# FRONT-UNIT.net
KiCad netlist of a schematic drawn in Altium Designer
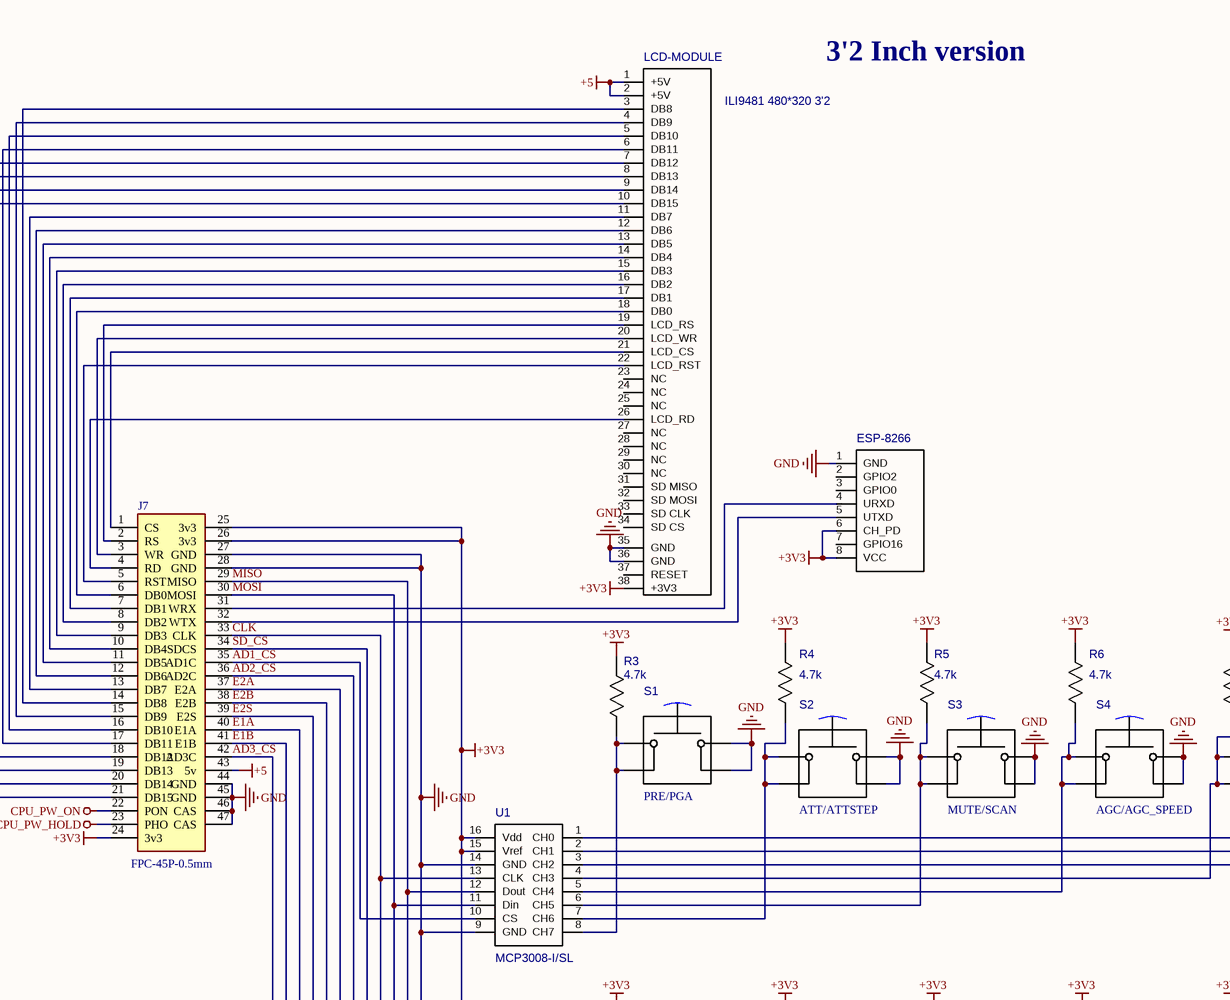
[diagram p0: FRONT-UNIT.SchDoc, top left]
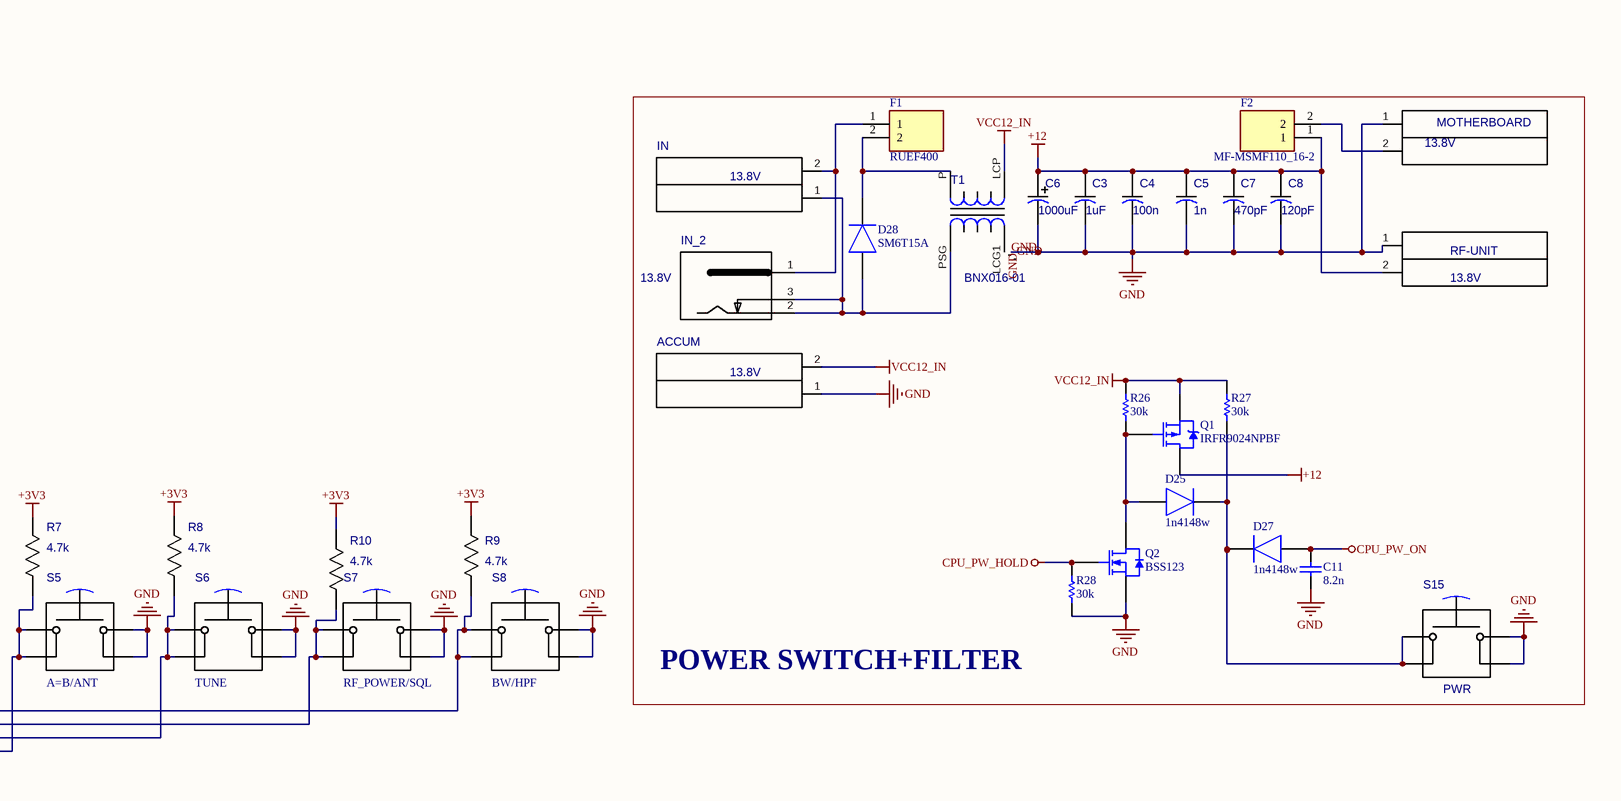
[diagram p1: FRONT-UNIT.SchDoc, top right]
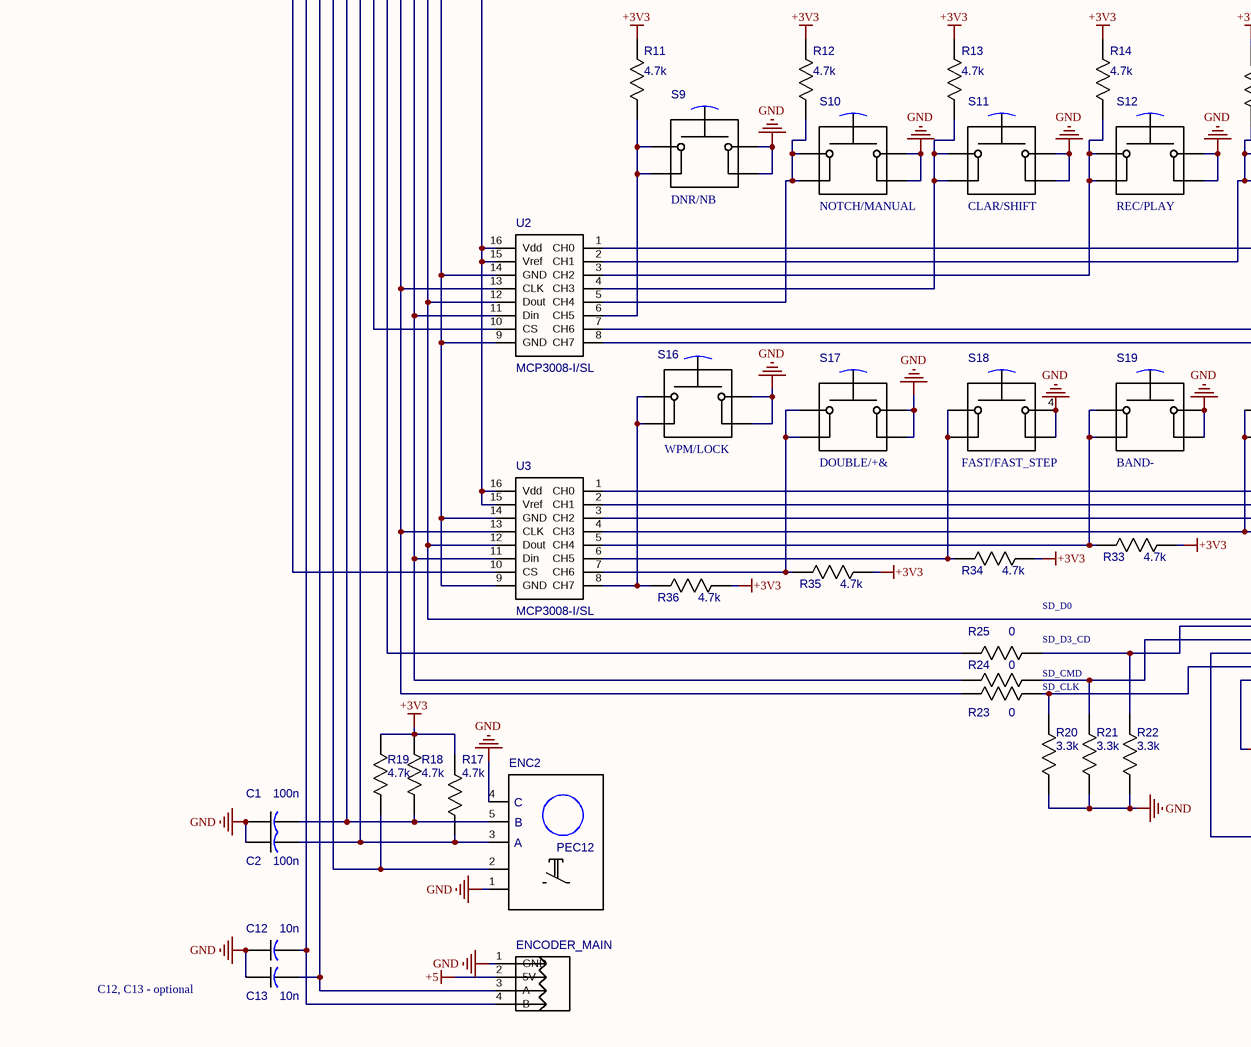
[diagram p2: FRONT-UNIT.SchDoc, bottom left]
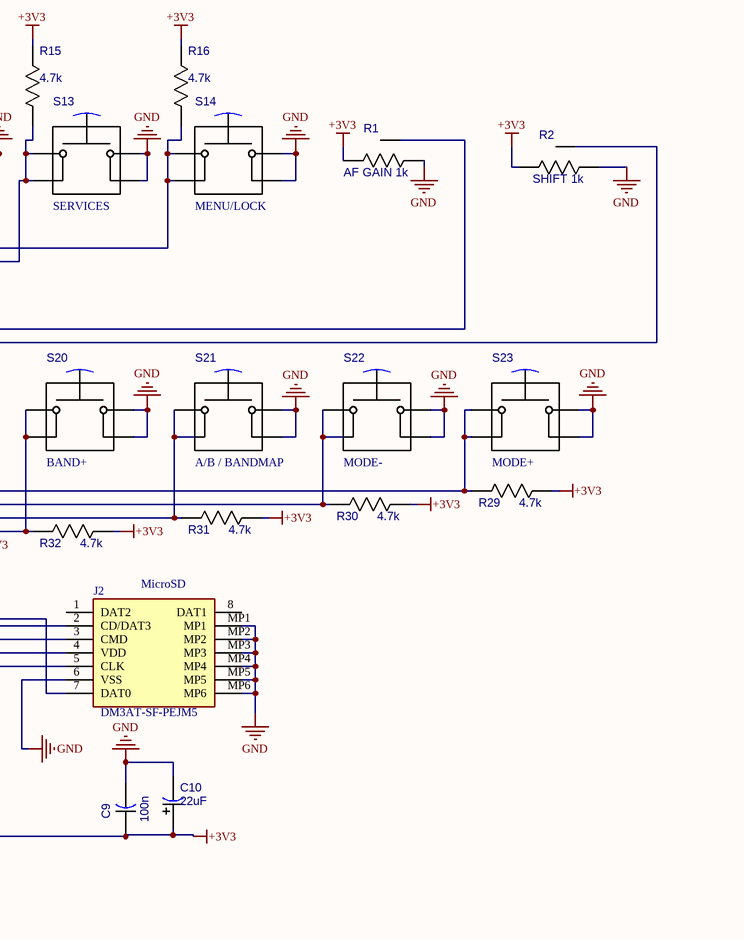
[diagram p3: FRONT-UNIT.SchDoc, bottom right]

(export (version "E")
  (design (tool "Eeschema 10.0.6"))
  (components
    (comp (ref "ACCUM")
      (value "13.8V")
      (footprint "JX2")
      (description "JX2")
      (libsource (lib "*") (part "JX2"))
    )
    (comp (ref "C1")
      (value "100n")
      (footprint "CAP_0805")
      (description "CAP_0805")
      (libsource (lib "*") (part "CAP_0805"))
    )
    (comp (ref "C2")
      (value "100n")
      (footprint "CAP_0805")
      (description "CAP_0805")
      (libsource (lib "*") (part "CAP_0805"))
    )
    (comp (ref "C3")
      (value "1uF")
      (footprint "CAP_1206")
      (description "CAP_1206")
      (libsource (lib "*") (part "CAP_1206"))
    )
    (comp (ref "C4")
      (value "100n")
      (footprint "CAP_1206")
      (description "CAP_1206")
      (libsource (lib "*") (part "CAP_1206"))
    )
    (comp (ref "C5")
      (value "1n")
      (footprint "CAP_1206")
      (description "CAP_1206")
      (libsource (lib "*") (part "CAP_1206"))
    )
    (comp (ref "C6")
      (value "1000uF")
      (footprint "CAP250RP")
      (description "CAP250RP")
      (libsource (lib "*") (part "CAP250RP"))
    )
    (comp (ref "C7")
      (value "470pF")
      (footprint "CAP_1206")
      (description "CAP_1206")
      (libsource (lib "*") (part "CAP_1206"))
    )
    (comp (ref "C8")
      (value "120pF")
      (footprint "CAP_1206")
      (description "CAP_1206")
      (libsource (lib "*") (part "CAP_1206"))
    )
    (comp (ref "C9")
      (value "100n")
      (footprint "CAP_0805")
      (description "CAP_0805")
      (libsource (lib "*") (part "CAP_0805"))
    )
    (comp (ref "C10")
      (value "22uF")
      (footprint "EEEFC_sizeB")
      (description "EEEFC_sizeB")
      (libsource (lib "*") (part "EEEFC_sizeB"))
    )
    (comp (ref "C11")
      (value "8.2n")
      (footprint "CAPC2013X94X50LL20T25")
      (description "CAP_1206")
      (fields
        (field (name "MANUFACTURER") "AVX Interconnect / Elco")
        (field (name "PART NUMBER") "08055C822KAT2A")
      )
      (libsource (lib "Altium Content Vault") (part "CAP"))
    )
    (comp (ref "C12")
      (value "10n")
      (footprint "CAP_0805")
      (description "CAP_0805")
      (libsource (lib "*") (part "CAP_0805"))
    )
    (comp (ref "C13")
      (value "10n")
      (footprint "CAP_0805")
      (description "CAP_0805")
      (libsource (lib "*") (part "CAP_0805"))
    )
    (comp (ref "D25")
      (value "1n4148w")
      (footprint "SamacSys:SOD3716X135N")
      (description "Diode")
      (libsource (lib "*") (part "1n4148w"))
    )
    (comp (ref "D27")
      (value "1n4148w")
      (footprint "SamacSys:SOD3716X135N")
      (description "Diode")
      (libsource (lib "*") (part "1n4148w"))
    )
    (comp (ref "D28")
      (value "SM6T15A")
      (footprint "SamacSys:SMBJ36CATR")
      (description "Diode")
      (fields (field (name "MOUSER PART NUMBER") "511-SM6T15A") (field (name "RS PART NUMBER") "4864915P"))
      (libsource (lib "*") (part "SM6T15A"))
    )
    (comp (ref "ENC2") (value "PEC12") (footprint "PEC12") (libsource (lib "*") (part "PEC12")))
    (comp (ref "ENCODER_MAIN")
      (value "OPTICAL ENCODER")
      (footprint "644456-4")
      (libsource (lib "*") (part "644456-4"))
    )
    (comp (ref "ESP-8266")
      (value "ESP-01 ESP8266")
      (footprint "ESP-01 ESP8266")
      (libsource (lib "*") (part "ESP-01 ESP8266"))
    )
    (comp (ref "F1")
      (value "RUEF400")
      (footprint "SamacSys:RUEF400")
      (description "Fuse")
      (fields (field (name "MOUSER PART NUMBER") "650-RUEF400") (field (name "RS PART NUMBER") "5176837P"))
      (libsource (lib "*") (part "RUEF400"))
    )
    (comp (ref "F2")
      (value "MF-MSMF110_16-2")
      (footprint "SamacSys:FUSC4632X85N")
      (description "Fuse")
      (fields
        (field (name "MANUFACTURER_PART_NUMBER") "MF-MSMF110/16-2")
        (field (name "MOUSER PART NUMBER") "652-MF-MSMF110/16-2")
      )
      (libsource (lib "*") (part "MF-MSMF110_16-2"))
    )
    (comp (ref "IN") (value "13.8V") (footprint "JX2") (description "JX2") (libsource (lib "*") (part "JX2")))
    (comp (ref "IN_2")
      (value "13.8V")
      (footprint "PJ-050B")
      (description "PJ-050B")
      (libsource (lib "*") (part "PJ-050B"))
    )
    (comp (ref "J2")
      (value "DM3AT-SF-PEJM5")
      (footprint "SamacSys:DM3ATSFPEJM5")
      (description "Connector")
      (libsource (lib "*") (part "DM3AT-SF-PEJM5"))
    )
    (comp (ref "J7")
      (value "FPC-45P-0.5mm")
      (footprint "FRONT-UNIT:FH12S45S05SH60")
      (description "Connector")
      (fields
        (field (name "MANUFACTURER_PART_NUMBER") "FH12S-45S-0.5SH(55)")
        (field (name "MOUSER PART NUMBER") "798-FH12S-45S-05SH55")
      )
      (libsource (lib "*") (part "FH12S-45S-0.5SH_55_"))
    )
    (comp (ref "LCD-MODULE")
      (value "ILI9481 480*320 3'2")
      (footprint "LCD-MODULE-3.2-480-320")
      (description "LCD-MODULE_3'2_480х320")
      (libsource (lib "FRONT-UNIT") (part "LCD-MODULE_3'2_480х320"))
    )
    (comp (ref "MOTHERBOARD")
      (value "13.8V")
      (footprint "JX2")
      (description "JX2")
      (libsource (lib "*") (part "JX2"))
    )
    (comp (ref "Q1")
      (value "IRFR9024NPBF")
      (footprint "ONSC-DPAK-3-369C-01_V")
      (description "IRFR9024NPBF, Транзистор, Р-канал 55В 11А")
      (fields (field (name "MANUFACTURER") "On Semiconductor") (field (name "PARTNUMBER") "NTD2955G"))
      (libsource (lib "Altium Content Vault") (part "ONSC-PMOS-G1S3D4-3_B"))
    )
    (comp (ref "Q2")
      (value "BSS123")
      (footprint "FAIR-SOT23-3_V")
      (fields (field (name "MANUFACTURER") "Fairchild"))
      (libsource (lib "Altium Content Vault") (part "NEMOS-GSD-3"))
    )
    (comp (ref "R1")
      (value "AF GAIN 1k")
      (footprint "PTV09")
      (description "Adjustable Resistor PTV09")
      (fields (field (name "Comment") "ptv09a-4225f-b102"))
      (libsource (lib "*") (part "PTV09"))
    )
    (comp (ref "R2")
      (value "SHIFT 1k")
      (footprint "PTV09")
      (description "Adjustable Resistor PTV09")
      (fields (field (name "Comment") "ptv09a-4225f-b102"))
      (libsource (lib "*") (part "PTV09"))
    )
    (comp (ref "R3")
      (value "4.7k")
      (footprint "RES_0805")
      (description "RES_0805")
      (libsource (lib "*") (part "RES_0805"))
    )
    (comp (ref "R4")
      (value "4.7k")
      (footprint "RES_0805")
      (description "RES_0805")
      (libsource (lib "*") (part "RES_0805"))
    )
    (comp (ref "R5")
      (value "4.7k")
      (footprint "RES_0805")
      (description "RES_0805")
      (libsource (lib "*") (part "RES_0805"))
    )
    (comp (ref "R6")
      (value "4.7k")
      (footprint "RES_0805")
      (description "RES_0805")
      (libsource (lib "*") (part "RES_0805"))
    )
    (comp (ref "R7")
      (value "4.7k")
      (footprint "RES_0805")
      (description "RES_0805")
      (libsource (lib "*") (part "RES_0805"))
    )
    (comp (ref "R8")
      (value "4.7k")
      (footprint "RES_0805")
      (description "RES_0805")
      (libsource (lib "*") (part "RES_0805"))
    )
    (comp (ref "R9")
      (value "4.7k")
      (footprint "RES_0805")
      (description "RES_0805")
      (libsource (lib "*") (part "RES_0805"))
    )
    (comp (ref "R10")
      (value "4.7k")
      (footprint "RES_0805")
      (description "RES_0805")
      (libsource (lib "*") (part "RES_0805"))
    )
    (comp (ref "R11")
      (value "4.7k")
      (footprint "RES_0805")
      (description "RES_0805")
      (libsource (lib "*") (part "RES_0805"))
    )
    (comp (ref "R12")
      (value "4.7k")
      (footprint "RES_0805")
      (description "RES_0805")
      (libsource (lib "*") (part "RES_0805"))
    )
    (comp (ref "R13")
      (value "4.7k")
      (footprint "RES_0805")
      (description "RES_0805")
      (libsource (lib "*") (part "RES_0805"))
    )
    (comp (ref "R14")
      (value "4.7k")
      (footprint "RES_0805")
      (description "RES_0805")
      (libsource (lib "*") (part "RES_0805"))
    )
    (comp (ref "R15")
      (value "4.7k")
      (footprint "RES_0805")
      (description "RES_0805")
      (libsource (lib "*") (part "RES_0805"))
    )
    (comp (ref "R16")
      (value "4.7k")
      (footprint "RES_0805")
      (description "RES_0805")
      (libsource (lib "*") (part "RES_0805"))
    )
    (comp (ref "R17")
      (value "4.7k")
      (footprint "RES_0805")
      (description "RES_0805")
      (libsource (lib "*") (part "RES_0805"))
    )
    (comp (ref "R18")
      (value "4.7k")
      (footprint "RES_0805")
      (description "RES_0805")
      (libsource (lib "*") (part "RES_0805"))
    )
    (comp (ref "R19")
      (value "4.7k")
      (footprint "RES_0805")
      (description "RES_0805")
      (libsource (lib "*") (part "RES_0805"))
    )
    (comp (ref "R20")
      (value "3.3k")
      (footprint "RES_0805")
      (description "RES_0805")
      (libsource (lib "*") (part "RES_0805"))
    )
    (comp (ref "R21")
      (value "3.3k")
      (footprint "RES_0805")
      (description "RES_0805")
      (libsource (lib "*") (part "RES_0805"))
    )
    (comp (ref "R22")
      (value "3.3k")
      (footprint "RES_0805")
      (description "RES_0805")
      (libsource (lib "*") (part "RES_0805"))
    )
    (comp (ref "R23")
      (value "0")
      (footprint "RES_0805")
      (description "RES_0805")
      (libsource (lib "*") (part "RES_0805"))
    )
    (comp (ref "R24")
      (value "0")
      (footprint "RES_0805")
      (description "RES_0805")
      (libsource (lib "*") (part "RES_0805"))
    )
    (comp (ref "R25")
      (value "0")
      (footprint "RES_0805")
      (description "RES_0805")
      (libsource (lib "*") (part "RES_0805"))
    )
    (comp (ref "R26")
      (value "30k")
      (footprint "RESC2013X60X40NL20T25")
      (description "RES_0805")
      (fields (field (name "MANUFACTURER") "Panasonic") (field (name "PART NUMBER") "ERA-6AEB303V"))
      (libsource (lib "Altium Content Vault") (part "RES"))
    )
    (comp (ref "R27")
      (value "30k")
      (footprint "RESC2013X60X40NL20T25")
      (description "RES_0805")
      (fields (field (name "MANUFACTURER") "Panasonic") (field (name "PART NUMBER") "ERA-6AEB303V"))
      (libsource (lib "Altium Content Vault") (part "RES"))
    )
    (comp (ref "R28")
      (value "30k")
      (footprint "RESC2013X60X40NL20T25")
      (description "RES_0805")
      (fields (field (name "MANUFACTURER") "Panasonic") (field (name "PART NUMBER") "ERA-6AEB303V"))
      (libsource (lib "Altium Content Vault") (part "RES"))
    )
    (comp (ref "R29")
      (value "4.7k")
      (footprint "RES_0805")
      (description "RES_0805")
      (libsource (lib "*") (part "RES_0805"))
    )
    (comp (ref "R30")
      (value "4.7k")
      (footprint "RES_0805")
      (description "RES_0805")
      (libsource (lib "*") (part "RES_0805"))
    )
    (comp (ref "R31")
      (value "4.7k")
      (footprint "RES_0805")
      (description "RES_0805")
      (libsource (lib "*") (part "RES_0805"))
    )
    (comp (ref "R32")
      (value "4.7k")
      (footprint "RES_0805")
      (description "RES_0805")
      (libsource (lib "*") (part "RES_0805"))
    )
    (comp (ref "R33")
      (value "4.7k")
      (footprint "RES_0805")
      (description "RES_0805")
      (libsource (lib "*") (part "RES_0805"))
    )
    (comp (ref "R34")
      (value "4.7k")
      (footprint "RES_0805")
      (description "RES_0805")
      (libsource (lib "*") (part "RES_0805"))
    )
    (comp (ref "R35")
      (value "4.7k")
      (footprint "RES_0805")
      (description "RES_0805")
      (libsource (lib "*") (part "RES_0805"))
    )
    (comp (ref "R36")
      (value "4.7k")
      (footprint "RES_0805")
      (description "RES_0805")
      (libsource (lib "*") (part "RES_0805"))
    )
    (comp (ref "RF-UNIT")
      (value "13.8V")
      (footprint "JX2")
      (description "JX2")
      (libsource (lib "*") (part "JX2"))
    )
    (comp (ref "S1")
      (value "PTS645SK50LFS")
      (footprint "PTS645SK50LFS")
      (fields (field (name "LCSC PART #") "test"))
      (libsource (lib "*") (part "PTS645SK50LFS"))
    )
    (comp (ref "S2")
      (value "PTS645SK50LFS")
      (footprint "PTS645SK50LFS")
      (libsource (lib "*") (part "PTS645SK50LFS"))
    )
    (comp (ref "S3")
      (value "PTS645SK50LFS")
      (footprint "PTS645SK50LFS")
      (libsource (lib "*") (part "PTS645SK50LFS"))
    )
    (comp (ref "S4")
      (value "PTS645SK50LFS")
      (footprint "PTS645SK50LFS")
      (libsource (lib "*") (part "PTS645SK50LFS"))
    )
    (comp (ref "S5")
      (value "PTS645SK50LFS")
      (footprint "PTS645SK50LFS")
      (libsource (lib "*") (part "PTS645SK50LFS"))
    )
    (comp (ref "S6")
      (value "PTS645SK50LFS")
      (footprint "PTS645SK50LFS")
      (libsource (lib "*") (part "PTS645SK50LFS"))
    )
    (comp (ref "S7")
      (value "PTS645SK50LFS")
      (footprint "PTS645SK50LFS")
      (libsource (lib "*") (part "PTS645SK50LFS"))
    )
    (comp (ref "S8")
      (value "PTS645SK50LFS")
      (footprint "PTS645SK50LFS")
      (libsource (lib "*") (part "PTS645SK50LFS"))
    )
    (comp (ref "S9")
      (value "PTS645SK50LFS")
      (footprint "PTS645SK50LFS")
      (libsource (lib "*") (part "PTS645SK50LFS"))
    )
    (comp (ref "S10")
      (value "PTS645SK50LFS")
      (footprint "PTS645SK50LFS")
      (libsource (lib "*") (part "PTS645SK50LFS"))
    )
    (comp (ref "S11")
      (value "PTS645SK50LFS")
      (footprint "PTS645SK50LFS")
      (libsource (lib "*") (part "PTS645SK50LFS"))
    )
    (comp (ref "S12")
      (value "PTS645SK50LFS")
      (footprint "PTS645SK50LFS")
      (libsource (lib "*") (part "PTS645SK50LFS"))
    )
    (comp (ref "S13")
      (value "PTS645SK50LFS")
      (footprint "PTS645SK50LFS")
      (libsource (lib "*") (part "PTS645SK50LFS"))
    )
    (comp (ref "S14")
      (value "PTS645SK50LFS")
      (footprint "PTS645SK50LFS")
      (libsource (lib "*") (part "PTS645SK50LFS"))
    )
    (comp (ref "S15")
      (value "PWR")
      (footprint "PTS645SK50LFS")
      (description "PTS645SK50LFS")
      (libsource (lib "*") (part "PTS645SK50LFS"))
    )
    (comp (ref "S16")
      (value "PTS645SK50LFS")
      (footprint "PTS645SK50LFS")
      (libsource (lib "*") (part "PTS645SK50LFS"))
    )
    (comp (ref "S17")
      (value "PTS645SK50LFS")
      (footprint "PTS645SK50LFS")
      (libsource (lib "*") (part "PTS645SK50LFS"))
    )
    (comp (ref "S18")
      (value "PTS645SK50LFS")
      (footprint "PTS645SK50LFS")
      (libsource (lib "") (part "PTS645SK50LFS_1"))
    )
    (comp (ref "S19")
      (value "PTS645SK50LFS")
      (footprint "PTS645SK50LFS")
      (libsource (lib "*") (part "PTS645SK50LFS"))
    )
    (comp (ref "S20")
      (value "PTS645SK50LFS")
      (footprint "PTS645SK50LFS")
      (libsource (lib "*") (part "PTS645SK50LFS"))
    )
    (comp (ref "S21")
      (value "PTS645SK50LFS")
      (footprint "PTS645SK50LFS")
      (libsource (lib "*") (part "PTS645SK50LFS"))
    )
    (comp (ref "S22")
      (value "PTS645SK50LFS")
      (footprint "PTS645SK50LFS")
      (libsource (lib "*") (part "PTS645SK50LFS"))
    )
    (comp (ref "S23")
      (value "PTS645SK50LFS")
      (footprint "PTS645SK50LFS")
      (libsource (lib "*") (part "PTS645SK50LFS"))
    )
    (comp (ref "T1")
      (value "BNX016-01")
      (footprint "TRANSF_ICORE")
      (libsource (lib "*") (part "TRANSF_ICORE"))
    )
    (comp (ref "U1")
      (value "MCP3008-I/SL")
      (footprint "MCP3008-I/SL")
      (libsource (lib "*") (part "MCP3008-I/SL"))
    )
    (comp (ref "U2")
      (value "MCP3008-I/SL")
      (footprint "MCP3008-I/SL")
      (libsource (lib "*") (part "MCP3008-I/SL"))
    )
    (comp (ref "U3")
      (value "MCP3008-I/SL")
      (footprint "MCP3008-I/SL")
      (libsource (lib "*") (part "MCP3008-I/SL"))
    )
  )
  (nets
    (net (code "1") (name "+3V3") (class "Default")
      (node (ref "C10") (pin "1") (pinfunction "PLUS_1") (pintype "passive"))
      (node (ref "C9") (pin "1") (pinfunction "1_1") (pintype "passive"))
      (node (ref "ESP-8266") (pin "6") (pinfunction "CH_PD_6") (pintype "passive"))
      (node (ref "ESP-8266") (pin "8") (pinfunction "VCC_8") (pintype "passive"))
      (node (ref "J2") (pin "4") (pinfunction "VDD_4") (pintype "passive"))
      (node (ref "J7") (pin "24") (pinfunction "3v3_24") (pintype "passive"))
      (node (ref "J7") (pin "25") (pinfunction "3v3_25") (pintype "passive"))
      (node (ref "J7") (pin "26") (pinfunction "3v3_26") (pintype "passive"))
      (node (ref "LCD-MODULE") (pin "38") (pinfunction "+3V3_38") (pintype "passive"))
      (node (ref "R1") (pin "1") (pinfunction "CW_1") (pintype "passive"))
      (node (ref "R10") (pin "2") (pinfunction "2_2") (pintype "passive"))
      (node (ref "R11") (pin "2") (pinfunction "2_2") (pintype "passive"))
      (node (ref "R12") (pin "2") (pinfunction "2_2") (pintype "passive"))
      (node (ref "R13") (pin "2") (pinfunction "2_2") (pintype "passive"))
      (node (ref "R14") (pin "2") (pinfunction "2_2") (pintype "passive"))
      (node (ref "R15") (pin "2") (pinfunction "2_2") (pintype "passive"))
      (node (ref "R16") (pin "2") (pinfunction "2_2") (pintype "passive"))
      (node (ref "R17") (pin "2") (pinfunction "2_2") (pintype "passive"))
      (node (ref "R18") (pin "2") (pinfunction "2_2") (pintype "passive"))
      (node (ref "R19") (pin "2") (pinfunction "2_2") (pintype "passive"))
      (node (ref "R2") (pin "1") (pinfunction "CW_1") (pintype "passive"))
      (node (ref "R29") (pin "2") (pinfunction "2_2") (pintype "passive"))
      (node (ref "R3") (pin "2") (pinfunction "2_2") (pintype "passive"))
      (node (ref "R30") (pin "2") (pinfunction "2_2") (pintype "passive"))
      (node (ref "R31") (pin "2") (pinfunction "2_2") (pintype "passive"))
      (node (ref "R32") (pin "2") (pinfunction "2_2") (pintype "passive"))
      (node (ref "R33") (pin "2") (pinfunction "2_2") (pintype "passive"))
      (node (ref "R34") (pin "2") (pinfunction "2_2") (pintype "passive"))
      (node (ref "R35") (pin "2") (pinfunction "2_2") (pintype "passive"))
      (node (ref "R36") (pin "2") (pinfunction "2_2") (pintype "passive"))
      (node (ref "R4") (pin "2") (pinfunction "2_2") (pintype "passive"))
      (node (ref "R5") (pin "2") (pinfunction "2_2") (pintype "passive"))
      (node (ref "R6") (pin "2") (pinfunction "2_2") (pintype "passive"))
      (node (ref "R7") (pin "2") (pinfunction "2_2") (pintype "passive"))
      (node (ref "R8") (pin "2") (pinfunction "2_2") (pintype "passive"))
      (node (ref "R9") (pin "2") (pinfunction "2_2") (pintype "passive"))
      (node (ref "U1") (pin "15") (pinfunction "Vref_15") (pintype "passive"))
      (node (ref "U1") (pin "16") (pinfunction "Vdd_16") (pintype "passive"))
      (node (ref "U2") (pin "15") (pinfunction "Vref_15") (pintype "passive"))
      (node (ref "U2") (pin "16") (pinfunction "Vdd_16") (pintype "passive"))
      (node (ref "U3") (pin "15") (pinfunction "Vref_15") (pintype "passive"))
      (node (ref "U3") (pin "16") (pinfunction "Vdd_16") (pintype "passive"))
    )
    (net (code "2") (name "+5") (class "Default")
      (node (ref "ENCODER_MAIN") (pin "2") (pinfunction "5V_2") (pintype "passive"))
      (node (ref "J7") (pin "43") (pinfunction "5v_43") (pintype "passive"))
      (node (ref "LCD-MODULE") (pin "1") (pinfunction "+5V_1") (pintype "passive"))
      (node (ref "LCD-MODULE") (pin "2") (pinfunction "+5V_2") (pintype "passive"))
    )
    (net (code "3") (name "+12") (class "Default")
      (node (ref "C3") (pin "1") (pinfunction "1_1") (pintype "passive"))
      (node (ref "C4") (pin "1") (pinfunction "1_1") (pintype "passive"))
      (node (ref "C5") (pin "1") (pinfunction "1_1") (pintype "passive"))
      (node (ref "C6") (pin "1") (pinfunction "PLUS_1") (pintype "passive"))
      (node (ref "C7") (pin "1") (pinfunction "1_1") (pintype "passive"))
      (node (ref "C8") (pin "1") (pinfunction "1_1") (pintype "passive"))
      (node (ref "F2") (pin "1") (pinfunction "1_1") (pintype "passive"))
      (node (ref "Q1") (pin "4") (pinfunction "D_4") (pintype "passive"))
      (node (ref "RF-UNIT") (pin "2") (pinfunction "1_2") (pintype "passive"))
    )
    (net (code "4") (name "/AD1_CS") (class "Default")
      (node (ref "J7") (pin "35") (pinfunction "AD1C_35") (pintype "passive"))
      (node (ref "U1") (pin "10") (pinfunction "CS_10") (pintype "passive"))
    )
    (net (code "5") (name "/AD2_CS") (class "Default")
      (node (ref "J7") (pin "36") (pinfunction "AD2C_36") (pintype "passive"))
      (node (ref "U2") (pin "10") (pinfunction "CS_10") (pintype "passive"))
    )
    (net (code "6") (name "/AD3_CS") (class "Default")
      (node (ref "J7") (pin "42") (pinfunction "AD3C_42") (pintype "passive"))
      (node (ref "U3") (pin "10") (pinfunction "CS_10") (pintype "passive"))
    )
    (net (code "7") (name "/CLK") (class "Default")
      (node (ref "J7") (pin "33") (pinfunction "CLK_33") (pintype "passive"))
      (node (ref "R23") (pin "2") (pinfunction "2_2") (pintype "passive"))
      (node (ref "U1") (pin "13") (pinfunction "CLK_13") (pintype "passive"))
      (node (ref "U2") (pin "13") (pinfunction "CLK_13") (pintype "passive"))
      (node (ref "U3") (pin "13") (pinfunction "CLK_13") (pintype "passive"))
    )
    (net (code "8") (name "/E1A") (class "Default")
      (node (ref "C13") (pin "2") (pinfunction "2_2") (pintype "passive"))
      (node (ref "ENCODER_MAIN") (pin "3") (pinfunction "A_3") (pintype "passive"))
      (node (ref "J7") (pin "40") (pinfunction "E1A_40") (pintype "passive"))
    )
    (net (code "9") (name "/E1B") (class "Default")
      (node (ref "C12") (pin "2") (pinfunction "2_2") (pintype "passive"))
      (node (ref "ENCODER_MAIN") (pin "4") (pinfunction "B_4") (pintype "passive"))
      (node (ref "J7") (pin "41") (pinfunction "E1B_41") (pintype "passive"))
    )
    (net (code "10") (name "/E2A") (class "Default")
      (node (ref "C2") (pin "2") (pinfunction "2_2") (pintype "passive"))
      (node (ref "ENC2") (pin "3") (pinfunction "A_3") (pintype "passive"))
      (node (ref "J7") (pin "37") (pinfunction "E2A_37") (pintype "passive"))
      (node (ref "R17") (pin "1") (pinfunction "1_1") (pintype "passive"))
    )
    (net (code "11") (name "/E2B") (class "Default")
      (node (ref "C1") (pin "2") (pinfunction "2_2") (pintype "passive"))
      (node (ref "ENC2") (pin "5") (pinfunction "B_5") (pintype "passive"))
      (node (ref "J7") (pin "38") (pinfunction "E2B_38") (pintype "passive"))
      (node (ref "R18") (pin "1") (pinfunction "1_1") (pintype "passive"))
    )
    (net (code "12") (name "/E2S") (class "Default")
      (node (ref "ENC2") (pin "2") (pinfunction "2_2") (pintype "passive"))
      (node (ref "J7") (pin "39") (pinfunction "E2S_39") (pintype "passive"))
      (node (ref "R19") (pin "1") (pinfunction "1_1") (pintype "passive"))
    )
    (net (code "13") (name "/MISO") (class "Default")
      (node (ref "J2") (pin "7") (pinfunction "DAT0_7") (pintype "passive"))
      (node (ref "J7") (pin "29") (pinfunction "MISO_29") (pintype "passive"))
      (node (ref "U1") (pin "12") (pinfunction "Dout_12") (pintype "passive"))
      (node (ref "U2") (pin "12") (pinfunction "Dout_12") (pintype "passive"))
      (node (ref "U3") (pin "12") (pinfunction "Dout_12") (pintype "passive"))
    )
    (net (code "14") (name "/MOSI") (class "Default")
      (node (ref "J7") (pin "30") (pinfunction "MOSI_30") (pintype "passive"))
      (node (ref "R24") (pin "2") (pinfunction "2_2") (pintype "passive"))
      (node (ref "U1") (pin "11") (pinfunction "Din_11") (pintype "passive"))
      (node (ref "U2") (pin "11") (pinfunction "Din_11") (pintype "passive"))
      (node (ref "U3") (pin "11") (pinfunction "Din_11") (pintype "passive"))
    )
    (net (code "15") (name "/SD_CS") (class "Default")
      (node (ref "J7") (pin "34") (pinfunction "SDCS_34") (pintype "passive"))
      (node (ref "R25") (pin "2") (pinfunction "2_2") (pintype "passive"))
    )
    (net (code "16") (name "CPU_PW_HOLD") (class "Default")
      (node (ref "J7") (pin "23") (pinfunction "PHO_23") (pintype "passive"))
      (node (ref "Q2") (pin "1") (pinfunction "G_1") (pintype "passive"))
      (node (ref "R28") (pin "2") (pinfunction "2_2") (pintype "passive"))
    )
    (net (code "17") (name "CPU_PW_ON") (class "Default")
      (node (ref "C11") (pin "2") (pinfunction "2_2") (pintype "passive"))
      (node (ref "D27") (pin "2") (pinfunction "A_2") (pintype "passive"))
      (node (ref "J7") (pin "22") (pinfunction "PON_22") (pintype "passive"))
    )
    (net (code "18") (name "GND") (class "Default")
      (node (ref "ACCUM") (pin "1") (pinfunction "2_1") (pintype "passive"))
      (node (ref "C1") (pin "1") (pinfunction "1_1") (pintype "passive"))
      (node (ref "C10") (pin "2") (pinfunction "MINUS_2") (pintype "passive"))
      (node (ref "C11") (pin "1") (pinfunction "1_1") (pintype "passive"))
      (node (ref "C12") (pin "1") (pinfunction "1_1") (pintype "passive"))
      (node (ref "C13") (pin "1") (pinfunction "1_1") (pintype "passive"))
      (node (ref "C2") (pin "1") (pinfunction "1_1") (pintype "passive"))
      (node (ref "C3") (pin "2") (pinfunction "2_2") (pintype "passive"))
      (node (ref "C4") (pin "2") (pinfunction "2_2") (pintype "passive"))
      (node (ref "C5") (pin "2") (pinfunction "2_2") (pintype "passive"))
      (node (ref "C6") (pin "2") (pinfunction "MINUS_2") (pintype "passive"))
      (node (ref "C7") (pin "2") (pinfunction "2_2") (pintype "passive"))
      (node (ref "C8") (pin "2") (pinfunction "2_2") (pintype "passive"))
      (node (ref "C9") (pin "2") (pinfunction "2_2") (pintype "passive"))
      (node (ref "ENC2") (pin "1") (pinfunction "1_1") (pintype "passive"))
      (node (ref "ENC2") (pin "4") (pinfunction "C_4") (pintype "passive"))
      (node (ref "ENCODER_MAIN") (pin "1") (pinfunction "GND_1") (pintype "passive"))
      (node (ref "ESP-8266") (pin "1") (pinfunction "GND_1") (pintype "passive"))
      (node (ref "J2") (pin "6") (pinfunction "VSS_6") (pintype "passive"))
      (node (ref "J2") (pin "MP1") (pinfunction "MP1_MP1") (pintype "passive"))
      (node (ref "J2") (pin "MP2") (pinfunction "MP2_MP2") (pintype "passive"))
      (node (ref "J2") (pin "MP3") (pinfunction "MP3_MP3") (pintype "passive"))
      (node (ref "J2") (pin "MP4") (pinfunction "MP4_MP4") (pintype "passive"))
      (node (ref "J2") (pin "MP5") (pinfunction "MP5_MP5") (pintype "passive"))
      (node (ref "J2") (pin "MP6") (pinfunction "MP6_MP6") (pintype "passive"))
      (node (ref "J7") (pin "27") (pinfunction "GND_27") (pintype "passive"))
      (node (ref "J7") (pin "28") (pinfunction "GND_28") (pintype "passive"))
      (node (ref "J7") (pin "44") (pinfunction "GND_44") (pintype "passive"))
      (node (ref "J7") (pin "45") (pinfunction "GND_45") (pintype "passive"))
      (node (ref "J7") (pin "46") (pinfunction "CAS_46") (pintype "passive"))
      (node (ref "J7") (pin "47") (pinfunction "CAS_47") (pintype "passive"))
      (node (ref "LCD-MODULE") (pin "35") (pinfunction "GND_35") (pintype "passive"))
      (node (ref "LCD-MODULE") (pin "36") (pinfunction "GND_36") (pintype "passive"))
      (node (ref "MOTHERBOARD") (pin "1") (pinfunction "2_1") (pintype "passive"))
      (node (ref "Q2") (pin "2") (pinfunction "S_2") (pintype "passive"))
      (node (ref "R1") (pin "3") (pinfunction "CCW_3") (pintype "passive"))
      (node (ref "R2") (pin "3") (pinfunction "CCW_3") (pintype "passive"))
      (node (ref "R20") (pin "1") (pinfunction "1_1") (pintype "passive"))
      (node (ref "R21") (pin "1") (pinfunction "1_1") (pintype "passive"))
      (node (ref "R22") (pin "1") (pinfunction "1_1") (pintype "passive"))
      (node (ref "R28") (pin "1") (pinfunction "1_1") (pintype "passive"))
      (node (ref "RF-UNIT") (pin "1") (pinfunction "2_1") (pintype "passive"))
      (node (ref "S1") (pin "3") (pinfunction "B_3") (pintype "passive"))
      (node (ref "S1") (pin "4") (pinfunction "B_4") (pintype "passive"))
      (node (ref "S10") (pin "3") (pinfunction "B_3") (pintype "passive"))
      (node (ref "S10") (pin "4") (pinfunction "B_4") (pintype "passive"))
      (node (ref "S11") (pin "3") (pinfunction "B_3") (pintype "passive"))
      (node (ref "S11") (pin "4") (pinfunction "B_4") (pintype "passive"))
      (node (ref "S12") (pin "3") (pinfunction "B_3") (pintype "passive"))
      (node (ref "S12") (pin "4") (pinfunction "B_4") (pintype "passive"))
      (node (ref "S13") (pin "3") (pinfunction "B_3") (pintype "passive"))
      (node (ref "S13") (pin "4") (pinfunction "B_4") (pintype "passive"))
      (node (ref "S14") (pin "3") (pinfunction "B_3") (pintype "passive"))
      (node (ref "S14") (pin "4") (pinfunction "B_4") (pintype "passive"))
      (node (ref "S15") (pin "3") (pinfunction "B_3") (pintype "passive"))
      (node (ref "S15") (pin "4") (pinfunction "B_4") (pintype "passive"))
      (node (ref "S16") (pin "3") (pinfunction "B_3") (pintype "passive"))
      (node (ref "S16") (pin "4") (pinfunction "B_4") (pintype "passive"))
      (node (ref "S17") (pin "3") (pinfunction "B_3") (pintype "passive"))
      (node (ref "S17") (pin "4") (pinfunction "B_4") (pintype "passive"))
      (node (ref "S18") (pin "3") (pinfunction "B_3") (pintype "passive"))
      (node (ref "S18") (pin "4") (pinfunction "B_4") (pintype "passive"))
      (node (ref "S19") (pin "3") (pinfunction "B_3") (pintype "passive"))
      (node (ref "S19") (pin "4") (pinfunction "B_4") (pintype "passive"))
      (node (ref "S2") (pin "3") (pinfunction "B_3") (pintype "passive"))
      (node (ref "S2") (pin "4") (pinfunction "B_4") (pintype "passive"))
      (node (ref "S20") (pin "3") (pinfunction "B_3") (pintype "passive"))
      (node (ref "S20") (pin "4") (pinfunction "B_4") (pintype "passive"))
      (node (ref "S21") (pin "3") (pinfunction "B_3") (pintype "passive"))
      (node (ref "S21") (pin "4") (pinfunction "B_4") (pintype "passive"))
      (node (ref "S22") (pin "3") (pinfunction "B_3") (pintype "passive"))
      (node (ref "S22") (pin "4") (pinfunction "B_4") (pintype "passive"))
      (node (ref "S23") (pin "3") (pinfunction "B_3") (pintype "passive"))
      (node (ref "S23") (pin "4") (pinfunction "B_4") (pintype "passive"))
      (node (ref "S3") (pin "3") (pinfunction "B_3") (pintype "passive"))
      (node (ref "S3") (pin "4") (pinfunction "B_4") (pintype "passive"))
      (node (ref "S4") (pin "3") (pinfunction "B_3") (pintype "passive"))
      (node (ref "S4") (pin "4") (pinfunction "B_4") (pintype "passive"))
      (node (ref "S5") (pin "3") (pinfunction "B_3") (pintype "passive"))
      (node (ref "S5") (pin "4") (pinfunction "B_4") (pintype "passive"))
      (node (ref "S6") (pin "3") (pinfunction "B_3") (pintype "passive"))
      (node (ref "S6") (pin "4") (pinfunction "B_4") (pintype "passive"))
      (node (ref "S7") (pin "3") (pinfunction "B_3") (pintype "passive"))
      (node (ref "S7") (pin "4") (pinfunction "B_4") (pintype "passive"))
      (node (ref "S8") (pin "3") (pinfunction "B_3") (pintype "passive"))
      (node (ref "S8") (pin "4") (pinfunction "B_4") (pintype "passive"))
      (node (ref "S9") (pin "3") (pinfunction "B_3") (pintype "passive"))
      (node (ref "S9") (pin "4") (pinfunction "B_4") (pintype "passive"))
      (node (ref "T1") (pin "LCG1") (pinfunction "S2_LCG1") (pintype "passive"))
      (node (ref "T1") (pin "LCG2") (pinfunction "0_LCG2") (pintype "passive"))
      (node (ref "T1") (pin "LCG3") (pinfunction "0_LCG3") (pintype "passive"))
      (node (ref "U1") (pin "14") (pinfunction "GND_14") (pintype "passive"))
      (node (ref "U1") (pin "9") (pinfunction "GND_9") (pintype "passive"))
      (node (ref "U2") (pin "14") (pinfunction "GND_14") (pintype "passive"))
      (node (ref "U2") (pin "9") (pinfunction "GND_9") (pintype "passive"))
      (node (ref "U3") (pin "14") (pinfunction "GND_14") (pintype "passive"))
      (node (ref "U3") (pin "9") (pinfunction "GND_9") (pintype "passive"))
    )
    (net (code "19") (name "Net-(D25-A)") (class "Default")
      (node (ref "D25") (pin "2") (pinfunction "A_2") (pintype "passive"))
      (node (ref "Q1") (pin "1") (pinfunction "G_1") (pintype "passive"))
      (node (ref "Q2") (pin "3") (pinfunction "D_3") (pintype "passive"))
      (node (ref "R26") (pin "1") (pinfunction "1_1") (pintype "passive"))
    )
    (net (code "20") (name "Net-(D25-K)") (class "Default")
      (node (ref "D25") (pin "1") (pinfunction "K_1") (pintype "passive"))
      (node (ref "D27") (pin "1") (pinfunction "K_1") (pintype "passive"))
      (node (ref "R27") (pin "1") (pinfunction "1_1") (pintype "passive"))
      (node (ref "S15") (pin "1") (pinfunction "A_1") (pintype "passive"))
      (node (ref "S15") (pin "2") (pinfunction "A_2") (pintype "passive"))
    )
    (net (code "21") (name "Net-(D28-A)") (class "Default")
      (node (ref "D28") (pin "2") (pinfunction "A_2") (pintype "passive"))
      (node (ref "IN") (pin "1") (pinfunction "2_1") (pintype "passive"))
      (node (ref "IN_2") (pin "2") (pinfunction "2_2") (pintype "passive"))
      (node (ref "IN_2") (pin "3") (pinfunction "3_3") (pintype "passive"))
      (node (ref "T1") (pin "PSG") (pinfunction "S1_PSG") (pintype "passive"))
    )
    (net (code "22") (name "Net-(D28-K)") (class "Default")
      (node (ref "D28") (pin "1") (pinfunction "K_1") (pintype "passive"))
      (node (ref "F1") (pin "2") (pinfunction "2_2") (pintype "passive"))
      (node (ref "T1") (pin "P") (pinfunction "P1_P") (pintype "passive"))
    )
    (net (code "23") (name "Net-(ESP-8266-URXD)") (class "Default")
      (node (ref "ESP-8266") (pin "4") (pinfunction "URXD_4") (pintype "passive"))
      (node (ref "J7") (pin "31") (pinfunction "WRX_31") (pintype "passive"))
    )
    (net (code "24") (name "Net-(ESP-8266-UTXD)") (class "Default")
      (node (ref "ESP-8266") (pin "5") (pinfunction "UTXD_5") (pintype "passive"))
      (node (ref "J7") (pin "32") (pinfunction "WTX_32") (pintype "passive"))
    )
    (net (code "25") (name "Net-(IN-1)") (class "Default")
      (node (ref "F1") (pin "1") (pinfunction "1_1") (pintype "passive"))
      (node (ref "IN") (pin "2") (pinfunction "1_2") (pintype "passive"))
      (node (ref "IN_2") (pin "1") (pinfunction "1_1") (pintype "passive"))
    )
    (net (code "26") (name "Net-(J2-CD{slash}DAT3)") (class "Default")
      (node (ref "J2") (pin "2") (pinfunction "CD/DAT3_2") (pintype "passive"))
      (node (ref "R22") (pin "2") (pinfunction "2_2") (pintype "passive"))
      (node (ref "R25") (pin "1") (pinfunction "1_1") (pintype "passive"))
    )
    (net (code "27") (name "Net-(J2-CLK)") (class "Default")
      (node (ref "J2") (pin "5") (pinfunction "CLK_5") (pintype "passive"))
      (node (ref "R20") (pin "2") (pinfunction "2_2") (pintype "passive"))
      (node (ref "R23") (pin "1") (pinfunction "1_1") (pintype "passive"))
    )
    (net (code "28") (name "Net-(J2-CMD)") (class "Default")
      (node (ref "J2") (pin "3") (pinfunction "CMD_3") (pintype "passive"))
      (node (ref "R21") (pin "2") (pinfunction "2_2") (pintype "passive"))
      (node (ref "R24") (pin "1") (pinfunction "1_1") (pintype "passive"))
    )
    (net (code "29") (name "Net-(J7-CS)") (class "Default")
      (node (ref "J7") (pin "1") (pinfunction "CS_1") (pintype "passive"))
      (node (ref "LCD-MODULE") (pin "21") (pinfunction "LCD_CS_21") (pintype "passive"))
    )
    (net (code "30") (name "Net-(J7-DB0)") (class "Default")
      (node (ref "J7") (pin "6") (pinfunction "DB0_6") (pintype "passive"))
      (node (ref "LCD-MODULE") (pin "18") (pinfunction "DB0_18") (pintype "passive"))
    )
    (net (code "31") (name "Net-(J7-DB1)") (class "Default")
      (node (ref "J7") (pin "7") (pinfunction "DB1_7") (pintype "passive"))
      (node (ref "LCD-MODULE") (pin "17") (pinfunction "DB1_17") (pintype "passive"))
    )
    (net (code "32") (name "Net-(J7-DB2)") (class "Default")
      (node (ref "J7") (pin "8") (pinfunction "DB2_8") (pintype "passive"))
      (node (ref "LCD-MODULE") (pin "16") (pinfunction "DB2_16") (pintype "passive"))
    )
    (net (code "33") (name "Net-(J7-DB3)") (class "Default")
      (node (ref "J7") (pin "9") (pinfunction "DB3_9") (pintype "passive"))
      (node (ref "LCD-MODULE") (pin "15") (pinfunction "DB3_15") (pintype "passive"))
    )
    (net (code "34") (name "Net-(J7-DB4)") (class "Default")
      (node (ref "J7") (pin "10") (pinfunction "DB4_10") (pintype "passive"))
      (node (ref "LCD-MODULE") (pin "14") (pinfunction "DB4_14") (pintype "passive"))
    )
    (net (code "35") (name "Net-(J7-DB5)") (class "Default")
      (node (ref "J7") (pin "11") (pinfunction "DB5_11") (pintype "passive"))
      (node (ref "LCD-MODULE") (pin "13") (pinfunction "DB5_13") (pintype "passive"))
    )
    (net (code "36") (name "Net-(J7-DB6)") (class "Default")
      (node (ref "J7") (pin "12") (pinfunction "DB6_12") (pintype "passive"))
      (node (ref "LCD-MODULE") (pin "12") (pinfunction "DB6_12") (pintype "passive"))
    )
    (net (code "37") (name "Net-(J7-DB7)") (class "Default")
      (node (ref "J7") (pin "13") (pinfunction "DB7_13") (pintype "passive"))
      (node (ref "LCD-MODULE") (pin "11") (pinfunction "DB7_11") (pintype "passive"))
    )
    (net (code "38") (name "Net-(J7-DB8)") (class "Default")
      (node (ref "J7") (pin "14") (pinfunction "DB8_14") (pintype "passive"))
      (node (ref "LCD-MODULE") (pin "3") (pinfunction "DB8_3") (pintype "passive"))
    )
    (net (code "39") (name "Net-(J7-DB9)") (class "Default")
      (node (ref "J7") (pin "15") (pinfunction "DB9_15") (pintype "passive"))
      (node (ref "LCD-MODULE") (pin "4") (pinfunction "DB9_4") (pintype "passive"))
    )
    (net (code "40") (name "Net-(J7-DB10)") (class "Default")
      (node (ref "J7") (pin "16") (pinfunction "DB10_16") (pintype "passive"))
      (node (ref "LCD-MODULE") (pin "5") (pinfunction "DB10_5") (pintype "passive"))
    )
    (net (code "41") (name "Net-(J7-DB11)") (class "Default")
      (node (ref "J7") (pin "17") (pinfunction "DB11_17") (pintype "passive"))
      (node (ref "LCD-MODULE") (pin "6") (pinfunction "DB11_6") (pintype "passive"))
    )
    (net (code "42") (name "Net-(J7-DB12)") (class "Default")
      (node (ref "J7") (pin "18") (pinfunction "DB12_18") (pintype "passive"))
      (node (ref "LCD-MODULE") (pin "7") (pinfunction "DB12_7") (pintype "passive"))
    )
    (net (code "43") (name "Net-(J7-DB13)") (class "Default")
      (node (ref "J7") (pin "19") (pinfunction "DB13_19") (pintype "passive"))
      (node (ref "LCD-MODULE") (pin "8") (pinfunction "DB13_8") (pintype "passive"))
    )
    (net (code "44") (name "Net-(J7-DB14)") (class "Default")
      (node (ref "J7") (pin "20") (pinfunction "DB14_20") (pintype "passive"))
      (node (ref "LCD-MODULE") (pin "9") (pinfunction "DB14_9") (pintype "passive"))
    )
    (net (code "45") (name "Net-(J7-DB15)") (class "Default")
      (node (ref "J7") (pin "21") (pinfunction "DB15_21") (pintype "passive"))
      (node (ref "LCD-MODULE") (pin "10") (pinfunction "DB15_10") (pintype "passive"))
    )
    (net (code "46") (name "Net-(J7-RD)") (class "Default")
      (node (ref "J7") (pin "4") (pinfunction "RD_4") (pintype "passive"))
      (node (ref "LCD-MODULE") (pin "26") (pinfunction "LCD_RD_26") (pintype "passive"))
    )
    (net (code "47") (name "Net-(J7-RS)") (class "Default")
      (node (ref "J7") (pin "2") (pinfunction "RS_2") (pintype "passive"))
      (node (ref "LCD-MODULE") (pin "19") (pinfunction "LCD_RS_19") (pintype "passive"))
    )
    (net (code "48") (name "Net-(J7-RST)") (class "Default")
      (node (ref "J7") (pin "5") (pinfunction "RST_5") (pintype "passive"))
      (node (ref "LCD-MODULE") (pin "22") (pinfunction "LCD_RST_22") (pintype "passive"))
    )
    (net (code "49") (name "Net-(J7-WR)") (class "Default")
      (node (ref "J7") (pin "3") (pinfunction "WR_3") (pintype "passive"))
      (node (ref "LCD-MODULE") (pin "20") (pinfunction "LCD_WR_20") (pintype "passive"))
    )
    (net (code "50") (name "Net-(MOTHERBOARD-1)") (class "Default")
      (node (ref "F2") (pin "2") (pinfunction "2_2") (pintype "passive"))
      (node (ref "MOTHERBOARD") (pin "2") (pinfunction "1_2") (pintype "passive"))
    )
    (net (code "51") (name "Net-(R1-W)") (class "Default")
      (node (ref "R1") (pin "2") (pinfunction "W_2") (pintype "passive"))
      (node (ref "U2") (pin "7") (pinfunction "CH6_7") (pintype "passive"))
    )
    (net (code "52") (name "Net-(R2-W)") (class "Default")
      (node (ref "R2") (pin "2") (pinfunction "W_2") (pintype "passive"))
      (node (ref "U2") (pin "8") (pinfunction "CH7_8") (pintype "passive"))
    )
    (net (code "53") (name "Net-(U1-CH0)") (class "Default")
      (node (ref "R9") (pin "1") (pinfunction "1_1") (pintype "passive"))
      (node (ref "S8") (pin "1") (pinfunction "A_1") (pintype "passive"))
      (node (ref "S8") (pin "2") (pinfunction "A_2") (pintype "passive"))
      (node (ref "U1") (pin "1") (pinfunction "CH0_1") (pintype "passive"))
    )
    (net (code "54") (name "Net-(U1-CH1)") (class "Default")
      (node (ref "R10") (pin "1") (pinfunction "1_1") (pintype "passive"))
      (node (ref "S7") (pin "1") (pinfunction "A_1") (pintype "passive"))
      (node (ref "S7") (pin "2") (pinfunction "A_2") (pintype "passive"))
      (node (ref "U1") (pin "2") (pinfunction "CH1_2") (pintype "passive"))
    )
    (net (code "55") (name "Net-(U1-CH2)") (class "Default")
      (node (ref "R8") (pin "1") (pinfunction "1_1") (pintype "passive"))
      (node (ref "S6") (pin "1") (pinfunction "A_1") (pintype "passive"))
      (node (ref "S6") (pin "2") (pinfunction "A_2") (pintype "passive"))
      (node (ref "U1") (pin "3") (pinfunction "CH2_3") (pintype "passive"))
    )
    (net (code "56") (name "Net-(U1-CH3)") (class "Default")
      (node (ref "R7") (pin "1") (pinfunction "1_1") (pintype "passive"))
      (node (ref "S5") (pin "1") (pinfunction "A_1") (pintype "passive"))
      (node (ref "S5") (pin "2") (pinfunction "A_2") (pintype "passive"))
      (node (ref "U1") (pin "4") (pinfunction "CH3_4") (pintype "passive"))
    )
    (net (code "57") (name "Net-(U1-CH4)") (class "Default")
      (node (ref "R6") (pin "1") (pinfunction "1_1") (pintype "passive"))
      (node (ref "S4") (pin "1") (pinfunction "A_1") (pintype "passive"))
      (node (ref "S4") (pin "2") (pinfunction "A_2") (pintype "passive"))
      (node (ref "U1") (pin "5") (pinfunction "CH4_5") (pintype "passive"))
    )
    (net (code "58") (name "Net-(U1-CH5)") (class "Default")
      (node (ref "R5") (pin "1") (pinfunction "1_1") (pintype "passive"))
      (node (ref "S3") (pin "1") (pinfunction "A_1") (pintype "passive"))
      (node (ref "S3") (pin "2") (pinfunction "A_2") (pintype "passive"))
      (node (ref "U1") (pin "6") (pinfunction "CH5_6") (pintype "passive"))
    )
    (net (code "59") (name "Net-(U1-CH6)") (class "Default")
      (node (ref "R4") (pin "1") (pinfunction "1_1") (pintype "passive"))
      (node (ref "S2") (pin "1") (pinfunction "A_1") (pintype "passive"))
      (node (ref "S2") (pin "2") (pinfunction "A_2") (pintype "passive"))
      (node (ref "U1") (pin "7") (pinfunction "CH6_7") (pintype "passive"))
    )
    (net (code "60") (name "Net-(U1-CH7)") (class "Default")
      (node (ref "R3") (pin "1") (pinfunction "1_1") (pintype "passive"))
      (node (ref "S1") (pin "1") (pinfunction "A_1") (pintype "passive"))
      (node (ref "S1") (pin "2") (pinfunction "A_2") (pintype "passive"))
      (node (ref "U1") (pin "8") (pinfunction "CH7_8") (pintype "passive"))
    )
    (net (code "61") (name "Net-(U2-CH0)") (class "Default")
      (node (ref "R16") (pin "1") (pinfunction "1_1") (pintype "passive"))
      (node (ref "S14") (pin "1") (pinfunction "A_1") (pintype "passive"))
      (node (ref "S14") (pin "2") (pinfunction "A_2") (pintype "passive"))
      (node (ref "U2") (pin "1") (pinfunction "CH0_1") (pintype "passive"))
    )
    (net (code "62") (name "Net-(U2-CH1)") (class "Default")
      (node (ref "R15") (pin "1") (pinfunction "1_1") (pintype "passive"))
      (node (ref "S13") (pin "1") (pinfunction "A_1") (pintype "passive"))
      (node (ref "S13") (pin "2") (pinfunction "A_2") (pintype "passive"))
      (node (ref "U2") (pin "2") (pinfunction "CH1_2") (pintype "passive"))
    )
    (net (code "63") (name "Net-(U2-CH2)") (class "Default")
      (node (ref "R14") (pin "1") (pinfunction "1_1") (pintype "passive"))
      (node (ref "S12") (pin "1") (pinfunction "A_1") (pintype "passive"))
      (node (ref "S12") (pin "2") (pinfunction "A_2") (pintype "passive"))
      (node (ref "U2") (pin "3") (pinfunction "CH2_3") (pintype "passive"))
    )
    (net (code "64") (name "Net-(U2-CH3)") (class "Default")
      (node (ref "R13") (pin "1") (pinfunction "1_1") (pintype "passive"))
      (node (ref "S11") (pin "1") (pinfunction "A_1") (pintype "passive"))
      (node (ref "S11") (pin "2") (pinfunction "A_2") (pintype "passive"))
      (node (ref "U2") (pin "4") (pinfunction "CH3_4") (pintype "passive"))
    )
    (net (code "65") (name "Net-(U2-CH4)") (class "Default")
      (node (ref "R12") (pin "1") (pinfunction "1_1") (pintype "passive"))
      (node (ref "S10") (pin "1") (pinfunction "A_1") (pintype "passive"))
      (node (ref "S10") (pin "2") (pinfunction "A_2") (pintype "passive"))
      (node (ref "U2") (pin "5") (pinfunction "CH4_5") (pintype "passive"))
    )
    (net (code "66") (name "Net-(U2-CH5)") (class "Default")
      (node (ref "R11") (pin "1") (pinfunction "1_1") (pintype "passive"))
      (node (ref "S9") (pin "1") (pinfunction "A_1") (pintype "passive"))
      (node (ref "S9") (pin "2") (pinfunction "A_2") (pintype "passive"))
      (node (ref "U2") (pin "6") (pinfunction "CH5_6") (pintype "passive"))
    )
    (net (code "67") (name "Net-(U3-CH0)") (class "Default")
      (node (ref "R29") (pin "1") (pinfunction "1_1") (pintype "passive"))
      (node (ref "S23") (pin "1") (pinfunction "A_1") (pintype "passive"))
      (node (ref "S23") (pin "2") (pinfunction "A_2") (pintype "passive"))
      (node (ref "U3") (pin "1") (pinfunction "CH0_1") (pintype "passive"))
    )
    (net (code "68") (name "Net-(U3-CH1)") (class "Default")
      (node (ref "R30") (pin "1") (pinfunction "1_1") (pintype "passive"))
      (node (ref "S22") (pin "1") (pinfunction "A_1") (pintype "passive"))
      (node (ref "S22") (pin "2") (pinfunction "A_2") (pintype "passive"))
      (node (ref "U3") (pin "2") (pinfunction "CH1_2") (pintype "passive"))
    )
    (net (code "69") (name "Net-(U3-CH2)") (class "Default")
      (node (ref "R31") (pin "1") (pinfunction "1_1") (pintype "passive"))
      (node (ref "S21") (pin "1") (pinfunction "A_1") (pintype "passive"))
      (node (ref "S21") (pin "2") (pinfunction "A_2") (pintype "passive"))
      (node (ref "U3") (pin "3") (pinfunction "CH2_3") (pintype "passive"))
    )
    (net (code "70") (name "Net-(U3-CH3)") (class "Default")
      (node (ref "R32") (pin "1") (pinfunction "1_1") (pintype "passive"))
      (node (ref "S20") (pin "1") (pinfunction "A_1") (pintype "passive"))
      (node (ref "S20") (pin "2") (pinfunction "A_2") (pintype "passive"))
      (node (ref "U3") (pin "4") (pinfunction "CH3_4") (pintype "passive"))
    )
    (net (code "71") (name "Net-(U3-CH4)") (class "Default")
      (node (ref "R33") (pin "1") (pinfunction "1_1") (pintype "passive"))
      (node (ref "S19") (pin "1") (pinfunction "A_1") (pintype "passive"))
      (node (ref "S19") (pin "2") (pinfunction "A_2") (pintype "passive"))
      (node (ref "U3") (pin "5") (pinfunction "CH4_5") (pintype "passive"))
    )
    (net (code "72") (name "Net-(U3-CH5)") (class "Default")
      (node (ref "R34") (pin "1") (pinfunction "1_1") (pintype "passive"))
      (node (ref "S18") (pin "1") (pinfunction "A_1") (pintype "passive"))
      (node (ref "S18") (pin "2") (pinfunction "A_2") (pintype "passive"))
      (node (ref "U3") (pin "6") (pinfunction "CH5_6") (pintype "passive"))
    )
    (net (code "73") (name "Net-(U3-CH6)") (class "Default")
      (node (ref "R35") (pin "1") (pinfunction "1_1") (pintype "passive"))
      (node (ref "S17") (pin "1") (pinfunction "A_1") (pintype "passive"))
      (node (ref "S17") (pin "2") (pinfunction "A_2") (pintype "passive"))
      (node (ref "U3") (pin "7") (pinfunction "CH6_7") (pintype "passive"))
    )
    (net (code "74") (name "Net-(U3-CH7)") (class "Default")
      (node (ref "R36") (pin "1") (pinfunction "1_1") (pintype "passive"))
      (node (ref "S16") (pin "1") (pinfunction "A_1") (pintype "passive"))
      (node (ref "S16") (pin "2") (pinfunction "A_2") (pintype "passive"))
      (node (ref "U3") (pin "8") (pinfunction "CH7_8") (pintype "passive"))
    )
    (net (code "75") (name "VCC12_IN") (class "Default")
      (node (ref "ACCUM") (pin "2") (pinfunction "1_2") (pintype "passive"))
      (node (ref "Q1") (pin "3") (pinfunction "S_3") (pintype "passive"))
      (node (ref "R26") (pin "2") (pinfunction "2_2") (pintype "passive"))
      (node (ref "R27") (pin "2") (pinfunction "2_2") (pintype "passive"))
      (node (ref "T1") (pin "LCP") (pinfunction "P2_LCP") (pintype "passive"))
    )
    (net (code "76") (name "unconnected-(ESP-8266-GPIO0-Pad3)") (class "Default")
      (node (ref "ESP-8266") (pin "3") (pinfunction "GPIO0_3") (pintype "passive"))
    )
    (net (code "77") (name "unconnected-(ESP-8266-GPIO2-Pad2)") (class "Default")
      (node (ref "ESP-8266") (pin "2") (pinfunction "GPIO2_2") (pintype "passive"))
    )
    (net (code "78") (name "unconnected-(ESP-8266-GPIO16-Pad7)") (class "Default")
      (node (ref "ESP-8266") (pin "7") (pinfunction "GPIO16_7") (pintype "passive"))
    )
    (net (code "79") (name "unconnected-(J2-DAT1-Pad8)") (class "Default")
      (node (ref "J2") (pin "8") (pinfunction "DAT1_8") (pintype "passive"))
    )
    (net (code "80") (name "unconnected-(J2-DAT2-Pad1)") (class "Default")
      (node (ref "J2") (pin "1") (pinfunction "DAT2_1") (pintype "passive"))
    )
    (net (code "81") (name "unconnected-(LCD-MODULE-NC-Pad23)") (class "Default")
      (node (ref "LCD-MODULE") (pin "23") (pinfunction "NC_23") (pintype "passive"))
    )
    (net (code "82") (name "unconnected-(LCD-MODULE-NC-Pad24)") (class "Default")
      (node (ref "LCD-MODULE") (pin "24") (pinfunction "NC_24") (pintype "passive"))
    )
    (net (code "83") (name "unconnected-(LCD-MODULE-NC-Pad25)") (class "Default")
      (node (ref "LCD-MODULE") (pin "25") (pinfunction "NC_25") (pintype "passive"))
    )
    (net (code "84") (name "unconnected-(LCD-MODULE-NC-Pad27)") (class "Default")
      (node (ref "LCD-MODULE") (pin "27") (pinfunction "NC_27") (pintype "passive"))
    )
    (net (code "85") (name "unconnected-(LCD-MODULE-NC-Pad28)") (class "Default")
      (node (ref "LCD-MODULE") (pin "28") (pinfunction "NC_28") (pintype "passive"))
    )
    (net (code "86") (name "unconnected-(LCD-MODULE-NC-Pad29)") (class "Default")
      (node (ref "LCD-MODULE") (pin "29") (pinfunction "NC_29") (pintype "passive"))
    )
    (net (code "87") (name "unconnected-(LCD-MODULE-NC-Pad30)") (class "Default")
      (node (ref "LCD-MODULE") (pin "30") (pinfunction "NC_30") (pintype "passive"))
    )
    (net (code "88") (name "unconnected-(LCD-MODULE-RESET-Pad37)") (class "Default")
      (node (ref "LCD-MODULE") (pin "37") (pinfunction "RESET_37") (pintype "passive"))
    )
    (net (code "89") (name "unconnected-(LCD-MODULE-SD_CLK-Pad33)") (class "Default")
      (node (ref "LCD-MODULE") (pin "33") (pinfunction "SD_CLK_33") (pintype "passive"))
    )
    (net (code "90") (name "unconnected-(LCD-MODULE-SD_CS-Pad34)") (class "Default")
      (node (ref "LCD-MODULE") (pin "34") (pinfunction "SD_CS_34") (pintype "passive"))
    )
    (net (code "91") (name "unconnected-(LCD-MODULE-SD_MISO-Pad31)") (class "Default")
      (node (ref "LCD-MODULE") (pin "31") (pinfunction "SD_MISO_31") (pintype "passive"))
    )
    (net (code "92") (name "unconnected-(LCD-MODULE-SD_MOSI-Pad32)") (class "Default")
      (node (ref "LCD-MODULE") (pin "32") (pinfunction "SD_MOSI_32") (pintype "passive"))
    )
  )
)
